# Lamp_Logic_Board.net
KiCad netlist of a schematic drawn in EAGLE
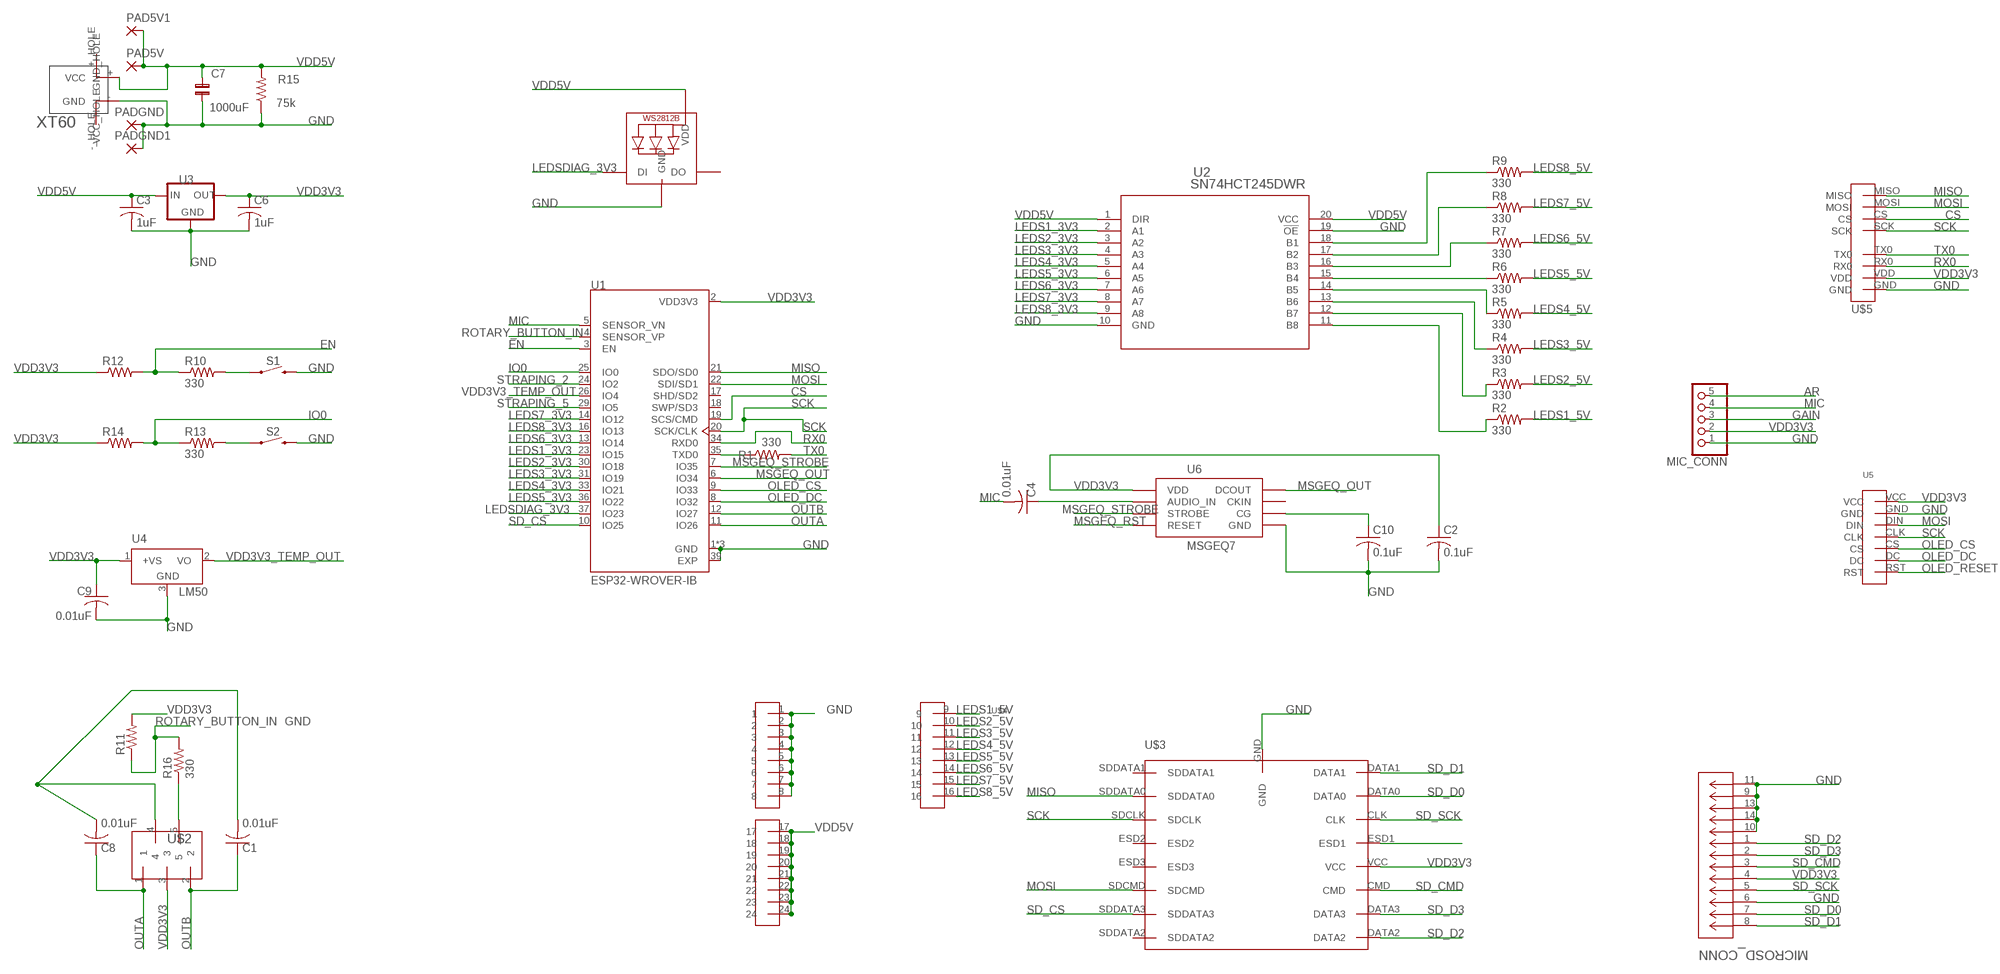
[diagram p0: schematic, sheet 1]

(export (version "E")
  (design (tool "Eeschema 10.0.6"))
  (components
    (comp (ref "C1")
      (value "0.01uF")
      (footprint "eagle-import:C0402")
      (libsource (lib "eagle-import") (part "C-USC0402"))
    )
    (comp (ref "C2")
      (value "0.1uF")
      (footprint "eagle-import:C0805")
      (libsource (lib "eagle-import") (part "C-USC0805"))
    )
    (comp (ref "C3")
      (value "1uF")
      (footprint "eagle-import:C0402")
      (libsource (lib "eagle-import") (part "C-USC0402"))
    )
    (comp (ref "C4")
      (value "0.01uF")
      (footprint "eagle-import:C0402")
      (libsource (lib "eagle-import") (part "C-USC0402"))
    )
    (comp (ref "C6")
      (value "1uF")
      (footprint "eagle-import:C0402")
      (libsource (lib "eagle-import") (part "C-USC0402"))
    )
    (comp (ref "C7")
      (value "1000uF")
      (footprint "eagle-import:ENP2,0-5")
      (libsource (lib "eagle-import") (part "C-BP-2,0X5"))
    )
    (comp (ref "C8")
      (value "0.01uF")
      (footprint "eagle-import:C0402")
      (libsource (lib "eagle-import") (part "C-USC0402"))
    )
    (comp (ref "C9")
      (value "0.01uF")
      (footprint "eagle-import:C0402")
      (libsource (lib "eagle-import") (part "C-USC0402"))
    )
    (comp (ref "C10")
      (value "0.1uF")
      (footprint "eagle-import:C0805")
      (libsource (lib "eagle-import") (part "C-USC0805"))
    )
    (comp (ref "LED1")
      (value "WS2812B5050")
      (footprint "eagle-import:WS2812B")
      (fields (field (name "MF") "Seeed Technology") (field (name "MP") "WS2812B"))
      (libsource (lib "eagle-import") (part "WS2812B5050"))
    )
    (comp (ref "MICROSD_CONN")
      (value "LLC")
      (footprint "eagle-import:CON00218_8")
      (libsource (lib "eagle-import") (part "LLC"))
    )
    (comp (ref "MIC_CONN")
      (value "PINHD-1X5")
      (footprint "eagle-import:1X05")
      (libsource (lib "eagle-import") (part "PINHD-1X5"))
    )
    (comp (ref "PAD5V")
      (value "SMD5")
      (footprint "eagle-import:SMD2,54-5,08")
      (libsource (lib "eagle-import") (part "SMD5"))
    )
    (comp (ref "PAD5V1")
      (value "SMD5")
      (footprint "eagle-import:SMD2,54-5,08")
      (libsource (lib "eagle-import") (part "SMD5"))
    )
    (comp (ref "PADGND")
      (value "SMD5")
      (footprint "eagle-import:SMD2,54-5,08")
      (libsource (lib "eagle-import") (part "SMD5"))
    )
    (comp (ref "PADGND1")
      (value "SMD5")
      (footprint "eagle-import:SMD2,54-5,08")
      (libsource (lib "eagle-import") (part "SMD5"))
    )
    (comp (ref "R1")
      (value "330")
      (footprint "eagle-import:R1206")
      (libsource (lib "eagle-import") (part "R-US_R1206"))
    )
    (comp (ref "R2")
      (value "330")
      (footprint "eagle-import:R1206")
      (libsource (lib "eagle-import") (part "R-US_R1206"))
    )
    (comp (ref "R3")
      (value "330")
      (footprint "eagle-import:R1206")
      (libsource (lib "eagle-import") (part "R-US_R1206"))
    )
    (comp (ref "R4")
      (value "330")
      (footprint "eagle-import:R1206")
      (libsource (lib "eagle-import") (part "R-US_R1206"))
    )
    (comp (ref "R5")
      (value "330")
      (footprint "eagle-import:R1206")
      (libsource (lib "eagle-import") (part "R-US_R1206"))
    )
    (comp (ref "R6")
      (value "330")
      (footprint "eagle-import:R1206")
      (libsource (lib "eagle-import") (part "R-US_R1206"))
    )
    (comp (ref "R7")
      (value "330")
      (footprint "eagle-import:R1206")
      (libsource (lib "eagle-import") (part "R-US_R1206"))
    )
    (comp (ref "R8")
      (value "330")
      (footprint "eagle-import:R1206")
      (libsource (lib "eagle-import") (part "R-US_R1206"))
    )
    (comp (ref "R9")
      (value "330")
      (footprint "eagle-import:R1206")
      (libsource (lib "eagle-import") (part "R-US_R1206"))
    )
    (comp (ref "R10")
      (value "330")
      (footprint "eagle-import:R1206")
      (libsource (lib "eagle-import") (part "R-US_R1206"))
    )
    (comp (ref "R11")
      (value "R-US_R0603")
      (footprint "eagle-import:R0603")
      (libsource (lib "eagle-import") (part "R-US_R0603"))
    )
    (comp (ref "R12")
      (value "R-US_R0603")
      (footprint "eagle-import:R0603")
      (libsource (lib "eagle-import") (part "R-US_R0603"))
    )
    (comp (ref "R13")
      (value "330")
      (footprint "eagle-import:R1206")
      (libsource (lib "eagle-import") (part "R-US_R1206"))
    )
    (comp (ref "R14")
      (value "R-US_R0603")
      (footprint "eagle-import:R0603")
      (libsource (lib "eagle-import") (part "R-US_R0603"))
    )
    (comp (ref "R15")
      (value "75k")
      (footprint "eagle-import:0309_12")
      (libsource (lib "eagle-import") (part "R-US_0309/12"))
    )
    (comp (ref "R16")
      (value "330")
      (footprint "eagle-import:R1206")
      (libsource (lib "eagle-import") (part "R-US_R1206"))
    )
    (comp (ref "S1")
      (value "MOMENTARY-SWITCH-SPST-SMD-6.0X3.5MM")
      (footprint "eagle-import:TACTILE_SWITCH_SMD_6.0X3.5MM")
      (libsource (lib "eagle-import") (part "MOMENTARY-SWITCH-SPST-SMD-6.0X3.5MM"))
    )
    (comp (ref "S2")
      (value "MOMENTARY-SWITCH-SPST-SMD-6.0X3.5MM")
      (footprint "eagle-import:TACTILE_SWITCH_SMD_6.0X3.5MM")
      (libsource (lib "eagle-import") (part "MOMENTARY-SWITCH-SPST-SMD-6.0X3.5MM"))
    )
    (comp (ref "U$1")
      (value "XT60")
      (footprint "eagle-import:XT60")
      (libsource (lib "eagle-import") (part "XT60"))
    )
    (comp (ref "U$2")
      (value "EN11-HSM1AF15")
      (footprint "eagle-import:EN11-HSM")
      (libsource (lib "eagle-import") (part "EN11-HSM1AF15"))
    )
    (comp (ref "U$3")
      (value "CM1624-08DE")
      (footprint "eagle-import:CM1624-08DE")
      (libsource (lib "eagle-import") (part "CM1624-08DE"))
    )
    (comp (ref "U$4")
      (value "3X8PINHEAD")
      (footprint "eagle-import:3X8PINHEAD")
      (libsource (lib "eagle-import") (part "3X8PINHEAD"))
    )
    (comp (ref "U$5")
      (value "2X4PINHEAD")
      (footprint "eagle-import:2X4PINHEAD")
      (libsource (lib "eagle-import") (part "2X4PINHEAD"))
    )
    (comp (ref "U1")
      (value "ESP32-WROVER-IB")
      (footprint "eagle-import:XCVR_ESP32-WROVER-I")
      (fields (field (name "MF") "Espressif Systems") (field (name "MP") "ESP32-WROVER-I"))
      (libsource (lib "eagle-import") (part "ESP32-WROVER-I"))
    )
    (comp (ref "U2")
      (value "SN74HCT245DWR")
      (footprint "eagle-import:DW20")
      (libsource (lib "eagle-import") (part "SN74HCT245DWR"))
    )
    (comp (ref "U3")
      (value "LM1117MP-1.8")
      (footprint "eagle-import:SOT223")
      (fields (field (name "MF") "Texas Instruments"))
      (libsource (lib "eagle-import") (part "LM1117?-MP1.8"))
    )
    (comp (ref "U4")
      (value "LM50")
      (footprint "eagle-import:SOT23")
      (libsource (lib "eagle-import") (part "LM50"))
    )
    (comp (ref "U5")
      (value "SPIOLED_STANDOFF")
      (footprint "eagle-import:SPIOLED_STADOFF")
      (libsource (lib "eagle-import") (part "SPIOLED_STANDOFF"))
    )
    (comp (ref "U6")
      (value "MSGEQ7DIL")
      (footprint "eagle-import:DIL-08")
      (fields
        (field (name "DIGI-KEY_PART_NUMBER") "1568-1544-ND")
        (field (name "MF") "SparkFun Electronics")
        (field (name "MP") "MSGEQ7")
      )
      (libsource (lib "eagle-import") (part "MSGEQ7DIL"))
    )
  )
  (nets
    (net (code "1") (name "/AR") (class "Default")
      (node (ref "MIC_CONN") (pin "5") (pinfunction "5_5") (pintype "passive"))
    )
    (net (code "2") (name "/CS") (class "Default")
      (node (ref "U$5") (pin "CS") (pinfunction "CS_CS") (pintype "bidirectional"))
      (node (ref "U1") (pin "19") (pinfunction "SCS/CMD_19") (pintype "bidirectional"))
    )
    (net (code "3") (name "/EN") (class "Default")
      (node (ref "R10") (pin "1") (pinfunction "1_1") (pintype "passive"))
      (node (ref "R12") (pin "2") (pinfunction "2_2") (pintype "passive"))
      (node (ref "U1") (pin "3") (pinfunction "EN_3") (pintype "input"))
    )
    (net (code "4") (name "/GAIN") (class "Default")
      (node (ref "MIC_CONN") (pin "3") (pinfunction "3_3") (pintype "passive"))
    )
    (net (code "5") (name "/GND") (class "Default")
      (node (ref "C1") (pin "2") (pinfunction "2_2") (pintype "passive"))
      (node (ref "C10") (pin "2") (pinfunction "2_2") (pintype "passive"))
      (node (ref "C2") (pin "2") (pinfunction "2_2") (pintype "passive"))
      (node (ref "C3") (pin "2") (pinfunction "2_2") (pintype "passive"))
      (node (ref "C6") (pin "2") (pinfunction "2_2") (pintype "passive"))
      (node (ref "C7") (pin "1") (pinfunction "1_1") (pintype "passive"))
      (node (ref "C8") (pin "2") (pinfunction "2_2") (pintype "passive"))
      (node (ref "C9") (pin "2") (pinfunction "2_2") (pintype "passive"))
      (node (ref "LED1") (pin "3-GND") (pinfunction "GND_3-GND") (pintype "power_in"))
      (node (ref "MICROSD_CONN") (pin "10") (pinfunction "10_10") (pintype "passive"))
      (node (ref "MICROSD_CONN") (pin "11") (pinfunction "11_11") (pintype "passive"))
      (node (ref "MICROSD_CONN") (pin "13") (pinfunction "13_13") (pintype "passive"))
      (node (ref "MICROSD_CONN") (pin "14") (pinfunction "14_14") (pintype "passive"))
      (node (ref "MICROSD_CONN") (pin "6") (pinfunction "6_6") (pintype "passive"))
      (node (ref "MICROSD_CONN") (pin "9") (pinfunction "9_9") (pintype "passive"))
      (node (ref "MIC_CONN") (pin "1") (pinfunction "1_1") (pintype "passive"))
      (node (ref "PADGND") (pin "1") (pinfunction "P_1") (pintype "passive"))
      (node (ref "PADGND1") (pin "1") (pinfunction "P_1") (pintype "passive"))
      (node (ref "R15") (pin "1") (pinfunction "1_1") (pintype "passive"))
      (node (ref "S1") (pin "2") (pinfunction "2_2") (pintype "passive"))
      (node (ref "S2") (pin "2") (pinfunction "2_2") (pintype "passive"))
      (node (ref "U$1") (pin "-") (pinfunction "GND_-") (pintype "bidirectional"))
      (node (ref "U$2") (pin "4") (pinfunction "4_4") (pintype "bidirectional"))
      (node (ref "U$3") (pin "GND") (pinfunction "GND_GND") (pintype "bidirectional"))
      (node (ref "U$4") (pin "1") (pinfunction "1_1") (pintype "bidirectional"))
      (node (ref "U$4") (pin "2") (pinfunction "2_2") (pintype "bidirectional"))
      (node (ref "U$4") (pin "3") (pinfunction "3_3") (pintype "bidirectional"))
      (node (ref "U$4") (pin "4") (pinfunction "4_4") (pintype "bidirectional"))
      (node (ref "U$4") (pin "5") (pinfunction "5_5") (pintype "bidirectional"))
      (node (ref "U$4") (pin "6") (pinfunction "6_6") (pintype "bidirectional"))
      (node (ref "U$4") (pin "7") (pinfunction "7_7") (pintype "bidirectional"))
      (node (ref "U$4") (pin "8") (pinfunction "8_8") (pintype "bidirectional"))
      (node (ref "U$5") (pin "GND") (pinfunction "GND_GND") (pintype "bidirectional"))
      (node (ref "U1") (pin "1") (pinfunction "GND_1") (pintype "power_in"))
      (node (ref "U1") (pin "15") (pinfunction "GND_15") (pintype "power_in"))
      (node (ref "U1") (pin "38") (pinfunction "GND_38") (pintype "power_in"))
      (node (ref "U1") (pin "39") (pinfunction "EXP_39") (pintype "power_in"))
      (node (ref "U2") (pin "10") (pinfunction "GND_10") (pintype "power_in"))
      (node (ref "U2") (pin "19") (pinfunction "~{OE}_19") (pintype "input"))
      (node (ref "U3") (pin "1") (pinfunction "GND_1") (pintype "input"))
      (node (ref "U4") (pin "3") (pinfunction "GND_3") (pintype "power_in"))
      (node (ref "U5") (pin "GND") (pinfunction "GND_GND") (pintype "bidirectional"))
      (node (ref "U6") (pin "2") (pinfunction "GND_2") (pintype "bidirectional"))
    )
    (net (code "6") (name "/IO0") (class "Default")
      (node (ref "R13") (pin "1") (pinfunction "1_1") (pintype "passive"))
      (node (ref "R14") (pin "2") (pinfunction "2_2") (pintype "passive"))
      (node (ref "U1") (pin "25") (pinfunction "IO0_25") (pintype "bidirectional"))
    )
    (net (code "7") (name "/LEDS1_3V3") (class "Default")
      (node (ref "U1") (pin "23") (pinfunction "IO15_23") (pintype "bidirectional"))
      (node (ref "U2") (pin "2") (pinfunction "A1_2") (pintype "bidirectional"))
    )
    (net (code "8") (name "/LEDS1_5V") (class "Default")
      (node (ref "R2") (pin "2") (pinfunction "2_2") (pintype "passive"))
      (node (ref "U$4") (pin "9") (pinfunction "9_9") (pintype "bidirectional"))
    )
    (net (code "9") (name "/LEDS2_3V3") (class "Default")
      (node (ref "U1") (pin "30") (pinfunction "IO18_30") (pintype "bidirectional"))
      (node (ref "U2") (pin "3") (pinfunction "A2_3") (pintype "bidirectional"))
    )
    (net (code "10") (name "/LEDS2_5V") (class "Default")
      (node (ref "R3") (pin "2") (pinfunction "2_2") (pintype "passive"))
      (node (ref "U$4") (pin "10") (pinfunction "10_10") (pintype "bidirectional"))
    )
    (net (code "11") (name "/LEDS3_3V3") (class "Default")
      (node (ref "U1") (pin "31") (pinfunction "IO19_31") (pintype "bidirectional"))
      (node (ref "U2") (pin "4") (pinfunction "A3_4") (pintype "bidirectional"))
    )
    (net (code "12") (name "/LEDS3_5V") (class "Default")
      (node (ref "R4") (pin "2") (pinfunction "2_2") (pintype "passive"))
      (node (ref "U$4") (pin "11") (pinfunction "11_11") (pintype "bidirectional"))
    )
    (net (code "13") (name "/LEDS4_3V3") (class "Default")
      (node (ref "U1") (pin "33") (pinfunction "IO21_33") (pintype "bidirectional"))
      (node (ref "U2") (pin "5") (pinfunction "A4_5") (pintype "bidirectional"))
    )
    (net (code "14") (name "/LEDS4_5V") (class "Default")
      (node (ref "R5") (pin "2") (pinfunction "2_2") (pintype "passive"))
      (node (ref "U$4") (pin "12") (pinfunction "12_12") (pintype "bidirectional"))
    )
    (net (code "15") (name "/LEDS5_3V3") (class "Default")
      (node (ref "U1") (pin "36") (pinfunction "IO22_36") (pintype "bidirectional"))
      (node (ref "U2") (pin "6") (pinfunction "A5_6") (pintype "bidirectional"))
    )
    (net (code "16") (name "/LEDS5_5V") (class "Default")
      (node (ref "R6") (pin "2") (pinfunction "2_2") (pintype "passive"))
      (node (ref "U$4") (pin "13") (pinfunction "13_13") (pintype "bidirectional"))
    )
    (net (code "17") (name "/LEDS6_3V3") (class "Default")
      (node (ref "U1") (pin "13") (pinfunction "IO14_13") (pintype "bidirectional"))
      (node (ref "U2") (pin "7") (pinfunction "A6_7") (pintype "bidirectional"))
    )
    (net (code "18") (name "/LEDS6_5V") (class "Default")
      (node (ref "R7") (pin "2") (pinfunction "2_2") (pintype "passive"))
      (node (ref "U$4") (pin "14") (pinfunction "14_14") (pintype "bidirectional"))
    )
    (net (code "19") (name "/LEDS7_3V3") (class "Default")
      (node (ref "U1") (pin "14") (pinfunction "IO12_14") (pintype "bidirectional"))
      (node (ref "U2") (pin "8") (pinfunction "A7_8") (pintype "bidirectional"))
    )
    (net (code "20") (name "/LEDS7_5V") (class "Default")
      (node (ref "R8") (pin "2") (pinfunction "2_2") (pintype "passive"))
      (node (ref "U$4") (pin "15") (pinfunction "15_15") (pintype "bidirectional"))
    )
    (net (code "21") (name "/LEDS8_3V3") (class "Default")
      (node (ref "U1") (pin "16") (pinfunction "IO13_16") (pintype "bidirectional"))
      (node (ref "U2") (pin "9") (pinfunction "A8_9") (pintype "bidirectional"))
    )
    (net (code "22") (name "/LEDS8_5V") (class "Default")
      (node (ref "R9") (pin "2") (pinfunction "2_2") (pintype "passive"))
      (node (ref "U$4") (pin "16") (pinfunction "16_16") (pintype "bidirectional"))
    )
    (net (code "23") (name "/LEDSDIAG_3V3") (class "Default")
      (node (ref "LED1") (pin "4-DIN") (pinfunction "DI_4-DIN") (pintype "input"))
      (node (ref "U1") (pin "37") (pinfunction "IO23_37") (pintype "bidirectional"))
    )
    (net (code "24") (name "/MIC") (class "Default")
      (node (ref "C4") (pin "2") (pinfunction "2_2") (pintype "passive"))
      (node (ref "MIC_CONN") (pin "4") (pinfunction "4_4") (pintype "passive"))
      (node (ref "U1") (pin "5") (pinfunction "SENSOR_VN_5") (pintype "input"))
    )
    (net (code "25") (name "/MISO") (class "Default")
      (node (ref "U$3") (pin "SDDATA0") (pinfunction "SDDATA0_SDDATA0") (pintype "bidirectional"))
      (node (ref "U$5") (pin "MISO") (pinfunction "MISO_MISO") (pintype "bidirectional"))
      (node (ref "U1") (pin "21") (pinfunction "SDO/SD0_21") (pintype "bidirectional"))
    )
    (net (code "26") (name "/MOSI") (class "Default")
      (node (ref "U$3") (pin "SDCMD") (pinfunction "SDCMD_SDCMD") (pintype "bidirectional"))
      (node (ref "U$5") (pin "MOSI") (pinfunction "MOSI_MOSI") (pintype "bidirectional"))
      (node (ref "U1") (pin "22") (pinfunction "SDI/SD1_22") (pintype "bidirectional"))
      (node (ref "U5") (pin "DIN") (pinfunction "DIN_DIN") (pintype "bidirectional"))
    )
    (net (code "27") (name "/MSGEQ_OUT") (class "Default")
      (node (ref "U1") (pin "6") (pinfunction "IO34_6") (pintype "input"))
      (node (ref "U6") (pin "3") (pinfunction "DCOUT_3") (pintype "bidirectional"))
    )
    (net (code "28") (name "/MSGEQ_RST") (class "Default")
      (node (ref "U6") (pin "7") (pinfunction "RESET_7") (pintype "input"))
    )
    (net (code "29") (name "/MSGEQ_STROBE") (class "Default")
      (node (ref "U1") (pin "7") (pinfunction "IO35_7") (pintype "input"))
      (node (ref "U6") (pin "4") (pinfunction "STROBE_4") (pintype "input"))
    )
    (net (code "30") (name "/OLED_CS") (class "Default")
      (node (ref "U1") (pin "9") (pinfunction "IO33_9") (pintype "bidirectional"))
      (node (ref "U5") (pin "CS") (pinfunction "CS_CS") (pintype "bidirectional"))
    )
    (net (code "31") (name "/OLED_DC") (class "Default")
      (node (ref "U1") (pin "8") (pinfunction "IO32_8") (pintype "bidirectional"))
      (node (ref "U5") (pin "DC") (pinfunction "DC_DC") (pintype "bidirectional"))
    )
    (net (code "32") (name "/OLED_RESET") (class "Default")
      (node (ref "U5") (pin "RST") (pinfunction "RST_RST") (pintype "bidirectional"))
    )
    (net (code "33") (name "/OUTA") (class "Default")
      (node (ref "C8") (pin "1") (pinfunction "1_1") (pintype "passive"))
      (node (ref "U$2") (pin "1") (pinfunction "1_1") (pintype "passive"))
      (node (ref "U1") (pin "11") (pinfunction "IO26_11") (pintype "bidirectional"))
    )
    (net (code "34") (name "/OUTB") (class "Default")
      (node (ref "C1") (pin "1") (pinfunction "1_1") (pintype "passive"))
      (node (ref "U$2") (pin "2") (pinfunction "2_2") (pintype "passive"))
      (node (ref "U1") (pin "12") (pinfunction "IO27_12") (pintype "bidirectional"))
    )
    (net (code "35") (name "/ROTARY_BUTTON_IN") (class "Default")
      (node (ref "R11") (pin "1") (pinfunction "1_1") (pintype "passive"))
      (node (ref "R16") (pin "2") (pinfunction "2_2") (pintype "passive"))
      (node (ref "U1") (pin "4") (pinfunction "SENSOR_VP_4") (pintype "input"))
    )
    (net (code "36") (name "/RX0") (class "Default")
      (node (ref "U$5") (pin "RX0") (pinfunction "RX0_RX0") (pintype "bidirectional"))
      (node (ref "U1") (pin "34") (pinfunction "RXD0_34") (pintype "bidirectional"))
    )
    (net (code "37") (name "/SCK") (class "Default")
      (node (ref "U$3") (pin "SDCLK") (pinfunction "SDCLK_SDCLK") (pintype "bidirectional"))
      (node (ref "U$5") (pin "SCK") (pinfunction "SCK_SCK") (pintype "bidirectional"))
      (node (ref "U1") (pin "20") (pinfunction "SCK/CLK_20") (pintype "bidirectional"))
      (node (ref "U5") (pin "CLK") (pinfunction "CLK_CLK") (pintype "bidirectional"))
    )
    (net (code "38") (name "/SD_CMD") (class "Default")
      (node (ref "MICROSD_CONN") (pin "3") (pinfunction "3_3") (pintype "passive"))
      (node (ref "U$3") (pin "CMD") (pinfunction "CMD_CMD") (pintype "bidirectional"))
    )
    (net (code "39") (name "/SD_CS") (class "Default")
      (node (ref "U$3") (pin "SDDATA3") (pinfunction "SDDATA3_SDDATA3") (pintype "bidirectional"))
      (node (ref "U1") (pin "10") (pinfunction "IO25_10") (pintype "bidirectional"))
    )
    (net (code "40") (name "/SD_D0") (class "Default")
      (node (ref "MICROSD_CONN") (pin "7") (pinfunction "7_7") (pintype "passive"))
      (node (ref "U$3") (pin "DATA0") (pinfunction "DATA0_DATA0") (pintype "bidirectional"))
    )
    (net (code "41") (name "/SD_D1") (class "Default")
      (node (ref "MICROSD_CONN") (pin "8") (pinfunction "8_8") (pintype "passive"))
      (node (ref "U$3") (pin "DATA1") (pinfunction "DATA1_DATA1") (pintype "bidirectional"))
    )
    (net (code "42") (name "/SD_D2") (class "Default")
      (node (ref "MICROSD_CONN") (pin "1") (pinfunction "1_1") (pintype "passive"))
      (node (ref "U$3") (pin "DATA2") (pinfunction "DATA2_DATA2") (pintype "bidirectional"))
    )
    (net (code "43") (name "/SD_D3") (class "Default")
      (node (ref "MICROSD_CONN") (pin "2") (pinfunction "2_2") (pintype "passive"))
      (node (ref "U$3") (pin "DATA3") (pinfunction "DATA3_DATA3") (pintype "bidirectional"))
    )
    (net (code "44") (name "/SD_SCK") (class "Default")
      (node (ref "MICROSD_CONN") (pin "5") (pinfunction "5_5") (pintype "passive"))
      (node (ref "U$3") (pin "CLK") (pinfunction "CLK_CLK") (pintype "bidirectional"))
    )
    (net (code "45") (name "/STRAPING_2") (class "Default")
      (node (ref "U1") (pin "24") (pinfunction "IO2_24") (pintype "bidirectional"))
    )
    (net (code "46") (name "/STRAPING_5") (class "Default")
      (node (ref "U1") (pin "29") (pinfunction "IO5_29") (pintype "bidirectional"))
    )
    (net (code "47") (name "/TX0") (class "Default")
      (node (ref "R1") (pin "2") (pinfunction "2_2") (pintype "passive"))
      (node (ref "U$5") (pin "TX0") (pinfunction "TX0_TX0") (pintype "bidirectional"))
    )
    (net (code "48") (name "/VDD3V3") (class "Default")
      (node (ref "C2") (pin "1") (pinfunction "1_1") (pintype "passive"))
      (node (ref "C6") (pin "1") (pinfunction "1_1") (pintype "passive"))
      (node (ref "C9") (pin "1") (pinfunction "1_1") (pintype "passive"))
      (node (ref "MICROSD_CONN") (pin "4") (pinfunction "4_4") (pintype "passive"))
      (node (ref "MIC_CONN") (pin "2") (pinfunction "2_2") (pintype "passive"))
      (node (ref "R11") (pin "2") (pinfunction "2_2") (pintype "passive"))
      (node (ref "R12") (pin "1") (pinfunction "1_1") (pintype "passive"))
      (node (ref "R14") (pin "1") (pinfunction "1_1") (pintype "passive"))
      (node (ref "U$2") (pin "3") (pinfunction "3_3") (pintype "passive"))
      (node (ref "U$3") (pin "VCC") (pinfunction "VCC_VCC") (pintype "bidirectional"))
      (node (ref "U$5") (pin "VDD") (pinfunction "VDD_VDD") (pintype "bidirectional"))
      (node (ref "U1") (pin "2") (pinfunction "VDD3V3_2") (pintype "power_in"))
      (node (ref "U3") (pin "2") (pinfunction "OUT_2") (pintype "passive"))
      (node (ref "U3") (pin "4") (pinfunction "OUT_4") (pintype "passive"))
      (node (ref "U4") (pin "1") (pinfunction "+VS_1") (pintype "input"))
      (node (ref "U5") (pin "VCC") (pinfunction "VCC_VCC") (pintype "bidirectional"))
      (node (ref "U6") (pin "1") (pinfunction "VDD_1") (pintype "input"))
    )
    (net (code "49") (name "/VDD3V3_TEMP_OUT") (class "Default")
      (node (ref "U1") (pin "26") (pinfunction "IO4_26") (pintype "bidirectional"))
      (node (ref "U4") (pin "2") (pinfunction "VO_2") (pintype "input"))
    )
    (net (code "50") (name "/VDD5V") (class "Default")
      (node (ref "C3") (pin "1") (pinfunction "1_1") (pintype "passive"))
      (node (ref "C7") (pin "2") (pinfunction "2_2") (pintype "passive"))
      (node (ref "LED1") (pin "1-VDD") (pinfunction "VDD_1-VDD") (pintype "power_in"))
      (node (ref "PAD5V") (pin "1") (pinfunction "P_1") (pintype "passive"))
      (node (ref "PAD5V1") (pin "1") (pinfunction "P_1") (pintype "passive"))
      (node (ref "R15") (pin "2") (pinfunction "2_2") (pintype "passive"))
      (node (ref "U$1") (pin "+") (pinfunction "VCC_+") (pintype "bidirectional"))
      (node (ref "U$4") (pin "17") (pinfunction "17_17") (pintype "bidirectional"))
      (node (ref "U$4") (pin "18") (pinfunction "18_18") (pintype "bidirectional"))
      (node (ref "U$4") (pin "19") (pinfunction "19_19") (pintype "bidirectional"))
      (node (ref "U$4") (pin "20") (pinfunction "20_20") (pintype "bidirectional"))
      (node (ref "U$4") (pin "21") (pinfunction "21_21") (pintype "bidirectional"))
      (node (ref "U$4") (pin "22") (pinfunction "22_22") (pintype "bidirectional"))
      (node (ref "U$4") (pin "23") (pinfunction "23_23") (pintype "bidirectional"))
      (node (ref "U$4") (pin "24") (pinfunction "24_24") (pintype "bidirectional"))
      (node (ref "U2") (pin "1") (pinfunction "DIR_1") (pintype "input"))
      (node (ref "U2") (pin "20") (pinfunction "VCC_20") (pintype "power_in"))
      (node (ref "U3") (pin "3") (pinfunction "IN_3") (pintype "input"))
    )
    (net (code "51") (name "Net-(R10-Pad2)") (class "Default")
      (node (ref "R10") (pin "2") (pinfunction "2_2") (pintype "passive"))
      (node (ref "S1") (pin "1") (pinfunction "1_1") (pintype "passive"))
    )
    (net (code "52") (name "Net-(R13-Pad2)") (class "Default")
      (node (ref "R13") (pin "2") (pinfunction "2_2") (pintype "passive"))
      (node (ref "S2") (pin "1") (pinfunction "1_1") (pintype "passive"))
    )
    (net (code "53") (name "Net-(R16-Pad1)") (class "Default")
      (node (ref "R16") (pin "1") (pinfunction "1_1") (pintype "passive"))
      (node (ref "U$2") (pin "5") (pinfunction "5_5") (pintype "bidirectional"))
    )
    (net (code "54") (name "Net-(U1-TXD0)") (class "Default")
      (node (ref "R1") (pin "1") (pinfunction "1_1") (pintype "passive"))
      (node (ref "U1") (pin "35") (pinfunction "TXD0_35") (pintype "bidirectional"))
    )
    (net (code "55") (name "Net-(U2-B1)") (class "Default")
      (node (ref "R9") (pin "1") (pinfunction "1_1") (pintype "passive"))
      (node (ref "U2") (pin "18") (pinfunction "B1_18") (pintype "bidirectional"))
    )
    (net (code "56") (name "Net-(U2-B2)") (class "Default")
      (node (ref "R8") (pin "1") (pinfunction "1_1") (pintype "passive"))
      (node (ref "U2") (pin "17") (pinfunction "B2_17") (pintype "bidirectional"))
    )
    (net (code "57") (name "Net-(U2-B3)") (class "Default")
      (node (ref "R7") (pin "1") (pinfunction "1_1") (pintype "passive"))
      (node (ref "U2") (pin "16") (pinfunction "B3_16") (pintype "bidirectional"))
    )
    (net (code "58") (name "Net-(U2-B4)") (class "Default")
      (node (ref "R6") (pin "1") (pinfunction "1_1") (pintype "passive"))
      (node (ref "U2") (pin "15") (pinfunction "B4_15") (pintype "bidirectional"))
    )
    (net (code "59") (name "Net-(U2-B5)") (class "Default")
      (node (ref "R5") (pin "1") (pinfunction "1_1") (pintype "passive"))
      (node (ref "U2") (pin "14") (pinfunction "B5_14") (pintype "bidirectional"))
    )
    (net (code "60") (name "Net-(U2-B6)") (class "Default")
      (node (ref "R4") (pin "1") (pinfunction "1_1") (pintype "passive"))
      (node (ref "U2") (pin "13") (pinfunction "B6_13") (pintype "bidirectional"))
    )
    (net (code "61") (name "Net-(U2-B7)") (class "Default")
      (node (ref "R3") (pin "1") (pinfunction "1_1") (pintype "passive"))
      (node (ref "U2") (pin "12") (pinfunction "B7_12") (pintype "bidirectional"))
    )
    (net (code "62") (name "Net-(U2-B8)") (class "Default")
      (node (ref "R2") (pin "1") (pinfunction "1_1") (pintype "passive"))
      (node (ref "U2") (pin "11") (pinfunction "B8_11") (pintype "bidirectional"))
    )
    (net (code "63") (name "Net-(U6-AUDIO_IN)") (class "Default")
      (node (ref "C4") (pin "1") (pinfunction "1_1") (pintype "passive"))
      (node (ref "U6") (pin "5") (pinfunction "AUDIO_IN_5") (pintype "input"))
    )
    (net (code "64") (name "Net-(U6-CG)") (class "Default")
      (node (ref "C10") (pin "1") (pinfunction "1_1") (pintype "passive"))
      (node (ref "U6") (pin "6") (pinfunction "CG_6") (pintype "bidirectional"))
    )
    (net (code "65") (name "unconnected-(LED1-DO-Pad2-DOUT)") (class "Default")
      (node (ref "LED1") (pin "2-DOUT") (pinfunction "DO_2-DOUT") (pintype "output"))
    )
    (net (code "66") (name "unconnected-(U$1-GND_HOLE-Pad-_HOLE)") (class "Default")
      (node (ref "U$1") (pin "-_HOLE") (pinfunction "GND_HOLE_-_HOLE") (pintype "bidirectional"))
    )
    (net (code "67") (name "unconnected-(U$1-VCC_HOLE-Pad+_HOLE)") (class "Default")
      (node (ref "U$1") (pin "+_HOLE") (pinfunction "VCC_HOLE_+_HOLE") (pintype "bidirectional"))
    )
    (net (code "68") (name "unconnected-(U$3-PadESD1)") (class "Default")
      (node (ref "U$3") (pin "ESD1") (pinfunction "ESD1_ESD1") (pintype "bidirectional"))
    )
    (net (code "69") (name "unconnected-(U$3-PadESD2)") (class "Default")
      (node (ref "U$3") (pin "ESD2") (pinfunction "ESD2_ESD2") (pintype "bidirectional"))
    )
    (net (code "70") (name "unconnected-(U$3-PadESD3)") (class "Default")
      (node (ref "U$3") (pin "ESD3") (pinfunction "ESD3_ESD3") (pintype "bidirectional"))
    )
    (net (code "71") (name "unconnected-(U$3-PadSDDATA1)") (class "Default")
      (node (ref "U$3") (pin "SDDATA1") (pinfunction "SDDATA1_SDDATA1") (pintype "bidirectional"))
    )
    (net (code "72") (name "unconnected-(U$3-PadSDDATA2)") (class "Default")
      (node (ref "U$3") (pin "SDDATA2") (pinfunction "SDDATA2_SDDATA2") (pintype "bidirectional"))
    )
    (net (code "73") (name "unconnected-(U1-SHD{slash}SD2-Pad17)") (class "Default")
      (node (ref "U1") (pin "17") (pinfunction "SHD/SD2_17") (pintype "bidirectional"))
    )
    (net (code "74") (name "unconnected-(U1-SWP{slash}SD3-Pad18)") (class "Default")
      (node (ref "U1") (pin "18") (pinfunction "SWP/SD3_18") (pintype "bidirectional"))
    )
    (net (code "75") (name "unconnected-(U6-CKIN-Pad8)") (class "Default")
      (node (ref "U6") (pin "8") (pinfunction "CKIN_8") (pintype "bidirectional"))
    )
  )
)
